# Handy_sense_v_1_0_2.net
KiCad netlist of a schematic drawn in EAGLE
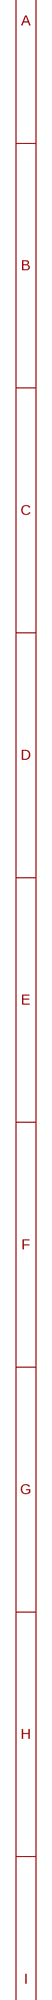
[diagram p0: schematic, sheet 1, part 1 of 2]
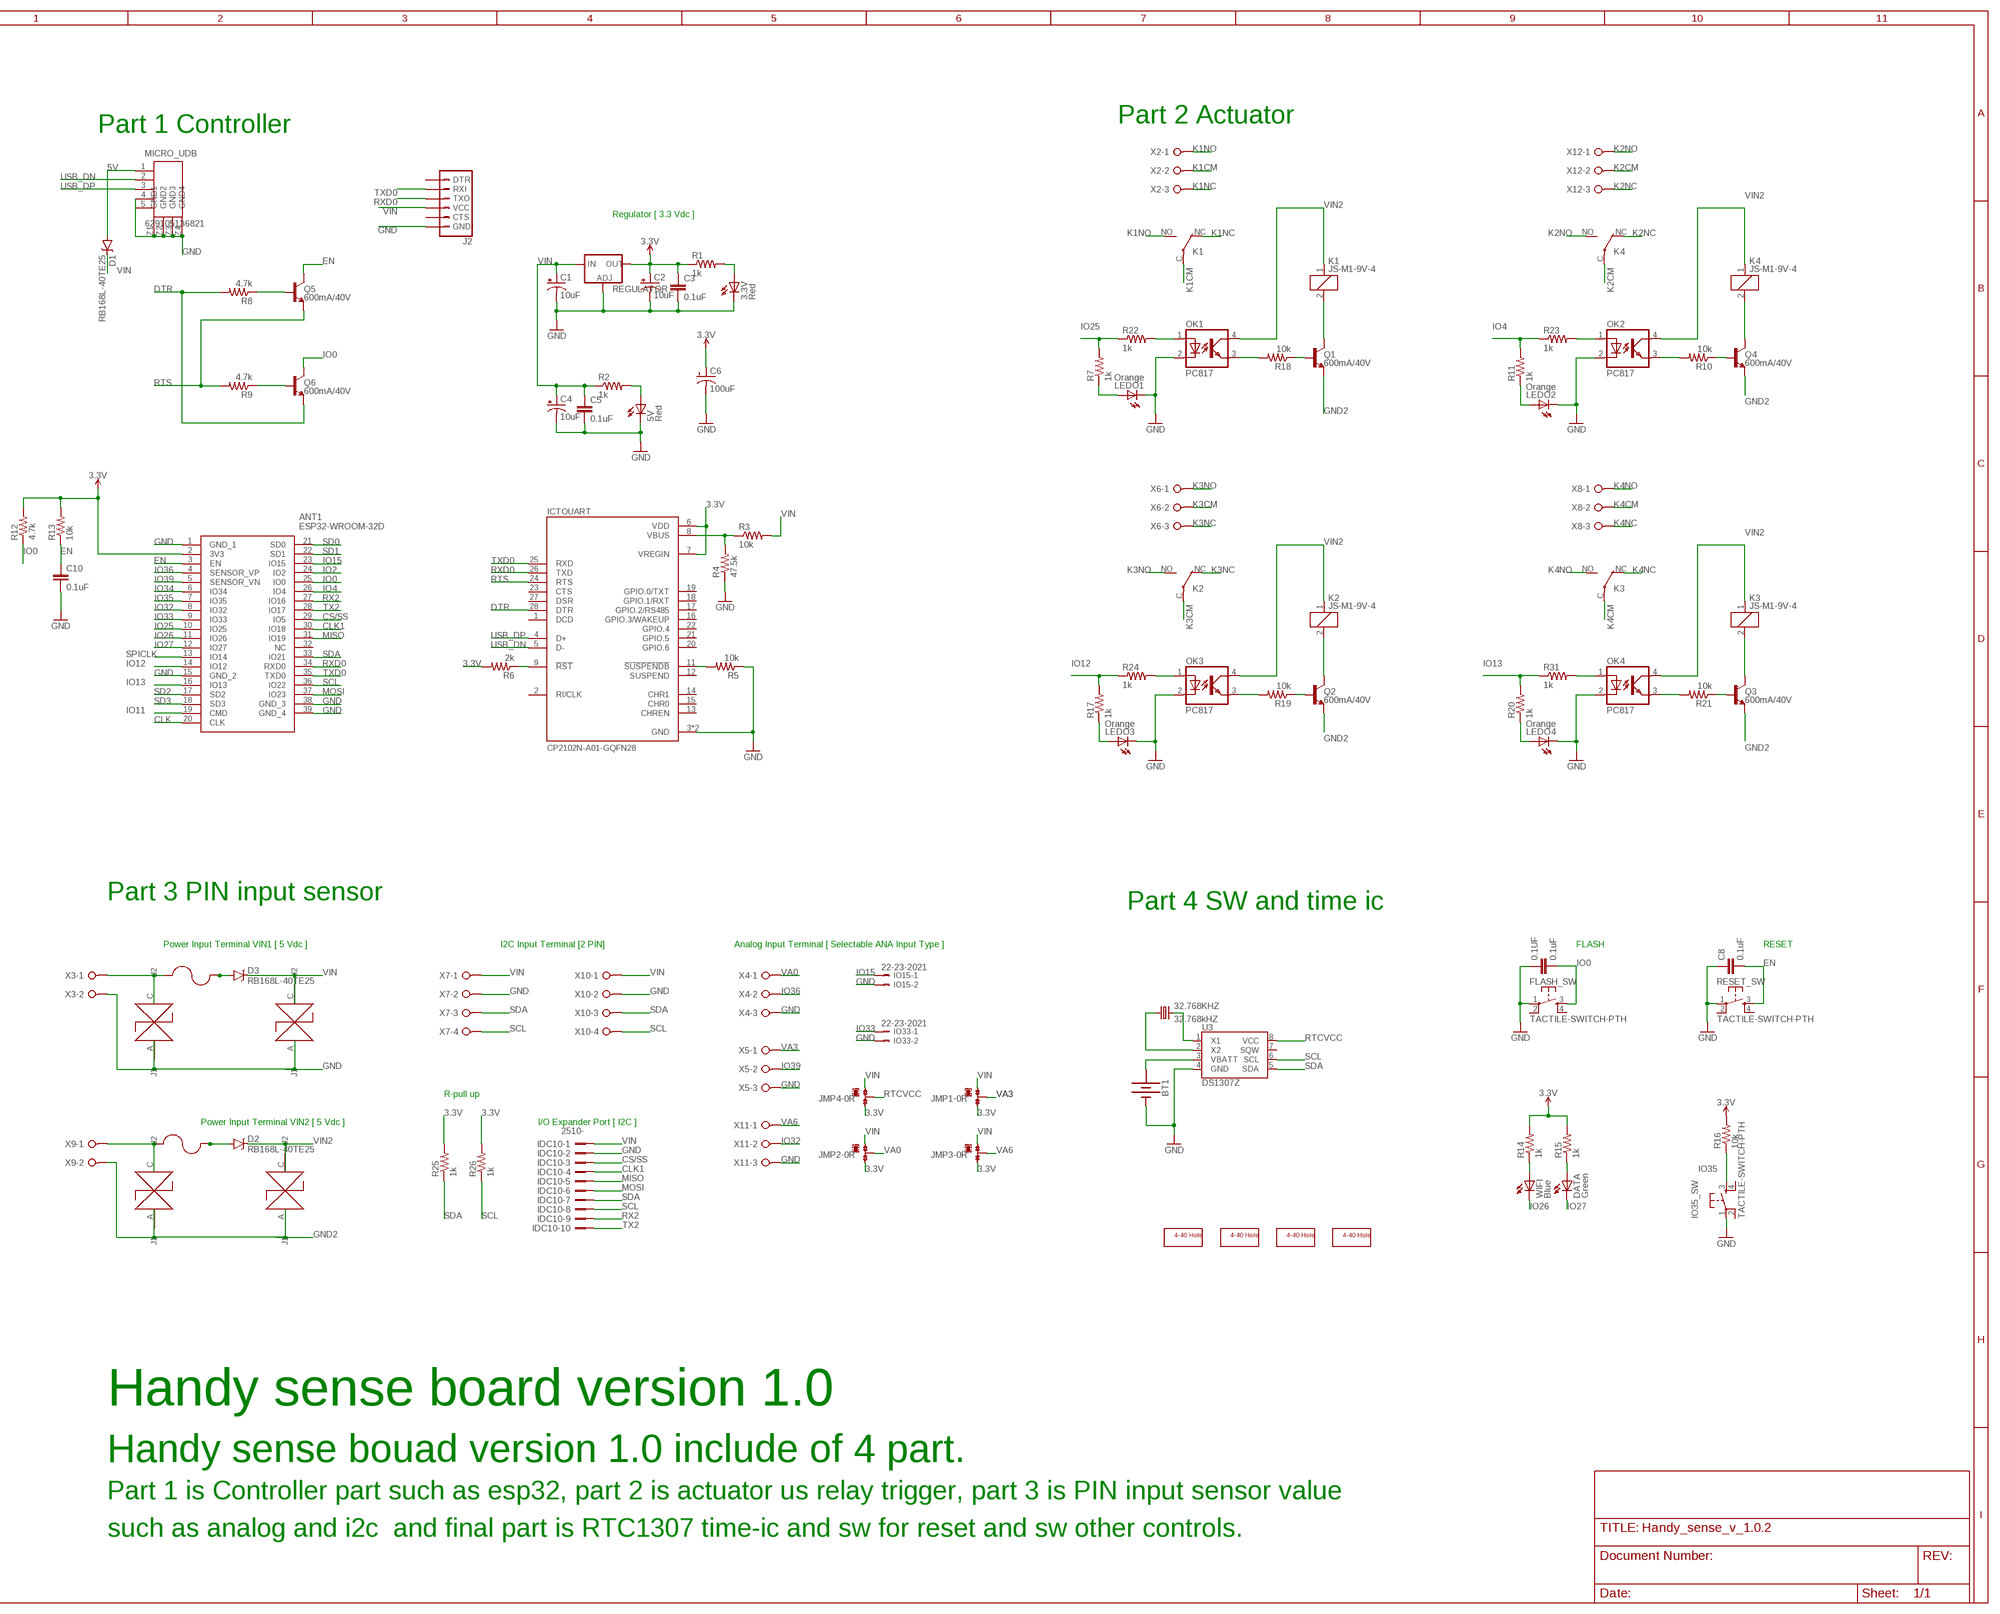
[diagram p1: schematic, sheet 1, part 2 of 2]

(export (version "E")
  (design (tool "Eeschema 10.0.6"))
  (components
    (comp (ref "0.1UF")
      (value "0.1uF")
      (footprint "eagle-import:0805")
      (libsource (lib "eagle-import") (part "CAP0805"))
    )
    (comp (ref "3.3V")
      (value "Red")
      (footprint "eagle-import:CHIPLED_0805")
      (libsource (lib "eagle-import") (part "LEDCHIPLED_0805"))
    )
    (comp (ref "5V")
      (value "Red")
      (footprint "eagle-import:CHIPLED_0805")
      (libsource (lib "eagle-import") (part "LEDCHIPLED_0805"))
    )
    (comp (ref "32.768KHZ")
      (value "32.768kHZ")
      (footprint "eagle-import:TC26H")
      (libsource (lib "eagle-import") (part "CRYSTALTC26H"))
    )
    (comp (ref "ANT1")
      (value "ESP32-WROOM-32D")
      (footprint "eagle-import:ESP32WROOM32D")
      (fields (field (name "MOUSER_PART_NUMBER") "356-ESP32WROOM-32D"))
      (libsource (lib "eagle-import") (part "ESP32-WROOM-32D"))
    )
    (comp (ref "BT1")
      (value "BATTERY-20MM_PTH_KIT")
      (footprint "eagle-import:BATTCOM_20MM_PTH_KIT")
      (libsource (lib "eagle-import") (part "BATTERY-20MM_PTH_KIT"))
    )
    (comp (ref "C1")
      (value "10uF")
      (footprint "eagle-import:EIA3216")
      (libsource (lib "eagle-import") (part "10UF-16V-10%(TANT)"))
    )
    (comp (ref "C2")
      (value "10uF")
      (footprint "eagle-import:EIA3216")
      (libsource (lib "eagle-import") (part "10UF-16V-10%(TANT)"))
    )
    (comp (ref "C3")
      (value "0.1uF")
      (footprint "eagle-import:0805")
      (libsource (lib "eagle-import") (part "CAP0805"))
    )
    (comp (ref "C4")
      (value "10uF")
      (footprint "eagle-import:EIA3216")
      (libsource (lib "eagle-import") (part "10UF-16V-10%(TANT)"))
    )
    (comp (ref "C5")
      (value "0.1uF")
      (footprint "eagle-import:0805")
      (libsource (lib "eagle-import") (part "CAP0805"))
    )
    (comp (ref "C6")
      (value "100uF")
      (footprint "eagle-import:EIA7343")
      (libsource (lib "eagle-import") (part "100UF-POLAR-EIA7343-16V-10%(TANT)"))
    )
    (comp (ref "C8")
      (value "0.1uF")
      (footprint "eagle-import:0805")
      (libsource (lib "eagle-import") (part "CAP0805"))
    )
    (comp (ref "C10")
      (value "0.1uF")
      (footprint "eagle-import:0805")
      (libsource (lib "eagle-import") (part "CAP0805"))
    )
    (comp (ref "D1")
      (value "RB168L-40TE25")
      (footprint "eagle-import:SMA-DIODE")
      (libsource (lib "eagle-import") (part "DIODE-SCHOTTKY-MBRA140"))
    )
    (comp (ref "D2")
      (value "RB168L-40TE25")
      (footprint "eagle-import:SMA-DIODE")
      (libsource (lib "eagle-import") (part "DIODE-SCHOTTKY-MBRA140"))
    )
    (comp (ref "D3")
      (value "RB168L-40TE25")
      (footprint "eagle-import:SMA-DIODE")
      (libsource (lib "eagle-import") (part "DIODE-SCHOTTKY-MBRA140"))
    )
    (comp (ref "DATA")
      (value "Green")
      (footprint "eagle-import:CHIPLED_0805")
      (libsource (lib "eagle-import") (part "LEDCHIPLED_0805"))
    )
    (comp (ref "FLASH_SW")
      (value "TACTILE-SWITCH-PTH")
      (footprint "eagle-import:TAC-SWITCH-PTH")
      (libsource (lib "eagle-import") (part "TACTILE-SWITCH-PTH"))
    )
    (comp (ref "HOLE0")
      (value "SCREW_HOLE_4-40")
      (footprint "eagle-import:SCREW_HOLE_4-40")
      (libsource (lib "eagle-import") (part "SCREW_HOLE_4-40"))
    )
    (comp (ref "HOLE1")
      (value "SCREW_HOLE_4-40")
      (footprint "eagle-import:SCREW_HOLE_4-40")
      (libsource (lib "eagle-import") (part "SCREW_HOLE_4-40"))
    )
    (comp (ref "HOLE2")
      (value "SCREW_HOLE_4-40")
      (footprint "eagle-import:SCREW_HOLE_4-40")
      (libsource (lib "eagle-import") (part "SCREW_HOLE_4-40"))
    )
    (comp (ref "HOLE3")
      (value "SCREW_HOLE_4-40")
      (footprint "eagle-import:SCREW_HOLE_4-40")
      (libsource (lib "eagle-import") (part "SCREW_HOLE_4-40"))
    )
    (comp (ref "ICTOUART")
      (value "CP2102N-A01-GQFN28")
      (footprint "eagle-import:QFN50P500X500X80-29N")
      (fields (field (name "MF") "Silicon Labs"))
      (libsource (lib "eagle-import") (part "CP2102N-A01-GQFN28"))
    )
    (comp (ref "IDC10")
      (value "2510-")
      (footprint "eagle-import:PAK100_2500-10")
      (fields (field (name "MF") "3M") (field (name "MPN") "2510-6002UB"))
      (libsource (lib "eagle-import") (part "2510-"))
    )
    (comp (ref "IO15")
      (value "22-23-2021")
      (footprint "eagle-import:22-23-2021")
      (fields (field (name "MF") "MOLEX"))
      (libsource (lib "eagle-import") (part "22-23-2021"))
    )
    (comp (ref "IO33")
      (value "22-23-2021")
      (footprint "eagle-import:22-23-2021")
      (fields (field (name "MF") "MOLEX"))
      (libsource (lib "eagle-import") (part "22-23-2021"))
    )
    (comp (ref "IO35_SW")
      (value "TACTILE-SWITCH-PTH")
      (footprint "eagle-import:TAC-SWITCH-PTH")
      (libsource (lib "eagle-import") (part "TACTILE-SWITCH-PTH"))
    )
    (comp (ref "J2")
      (value "6_PIN_SERIAL_TARGET_SILK")
      (footprint "eagle-import:1X06")
      (libsource (lib "eagle-import") (part "6_PIN_SERIAL_TARGET_SILK"))
    )
    (comp (ref "J28CA1")
      (value "SMBJ28CA")
      (footprint "eagle-import:DIOM505270X240")
      (libsource (lib "eagle-import") (part "SMBJ28CA"))
    )
    (comp (ref "J28CA3")
      (value "SMBJ28CA")
      (footprint "eagle-import:DIOM505270X240")
      (libsource (lib "eagle-import") (part "SMBJ28CA"))
    )
    (comp (ref "J28CA4")
      (value "SMBJ28CA")
      (footprint "eagle-import:DIOM505270X240")
      (libsource (lib "eagle-import") (part "SMBJ28CA"))
    )
    (comp (ref "J28CA6")
      (value "SMBJ28CA")
      (footprint "eagle-import:DIOM505270X240")
      (libsource (lib "eagle-import") (part "SMBJ28CA"))
    )
    (comp (ref "JMP1")
      (value "0R-JUMPB")
      (footprint "eagle-import:B0R-JMP")
      (libsource (lib "eagle-import") (part "0R-JUMPB"))
    )
    (comp (ref "JMP2")
      (value "0R-JUMPB")
      (footprint "eagle-import:B0R-JMP")
      (libsource (lib "eagle-import") (part "0R-JUMPB"))
    )
    (comp (ref "JMP3")
      (value "0R-JUMPB")
      (footprint "eagle-import:B0R-JMP")
      (libsource (lib "eagle-import") (part "0R-JUMPB"))
    )
    (comp (ref "JMP4")
      (value "0R-JUMPB")
      (footprint "eagle-import:B0R-JMP")
      (libsource (lib "eagle-import") (part "0R-JUMPB"))
    )
    (comp (ref "K1")
      (value "JS-M1-9V-4")
      (footprint "eagle-import:JS-M")
      (libsource (lib "eagle-import") (part "JS-M1-9V-4"))
    )
    (comp (ref "K2")
      (value "JS-M1-9V-4")
      (footprint "eagle-import:JS-M")
      (libsource (lib "eagle-import") (part "JS-M1-9V-4"))
    )
    (comp (ref "K3")
      (value "JS-M1-9V-4")
      (footprint "eagle-import:JS-M")
      (libsource (lib "eagle-import") (part "JS-M1-9V-4"))
    )
    (comp (ref "K4")
      (value "JS-M1-9V-4")
      (footprint "eagle-import:JS-M")
      (libsource (lib "eagle-import") (part "JS-M1-9V-4"))
    )
    (comp (ref "LEDO1")
      (value "Orange")
      (footprint "eagle-import:CHIPLED_0805")
      (libsource (lib "eagle-import") (part "LEDCHIPLED_0805"))
    )
    (comp (ref "LEDO2")
      (value "Orange")
      (footprint "eagle-import:CHIPLED_0805")
      (libsource (lib "eagle-import") (part "LEDCHIPLED_0805"))
    )
    (comp (ref "LEDO3")
      (value "Orange")
      (footprint "eagle-import:CHIPLED_0805")
      (libsource (lib "eagle-import") (part "LEDCHIPLED_0805"))
    )
    (comp (ref "LEDO4")
      (value "Orange")
      (footprint "eagle-import:CHIPLED_0805")
      (libsource (lib "eagle-import") (part "LEDCHIPLED_0805"))
    )
    (comp (ref "MICRO_UDB")
      (value "629105136821")
      (footprint "eagle-import:629105136821")
      (libsource (lib "eagle-import") (part "629105136821"))
    )
    (comp (ref "OK1")
      (value "PC817")
      (footprint "eagle-import:DIL04")
      (fields (field (name "MPN") "PC817X4J000F"))
      (libsource (lib "eagle-import") (part "PC817"))
    )
    (comp (ref "OK2")
      (value "PC817")
      (footprint "eagle-import:DIL04")
      (fields (field (name "MPN") "PC817X4J000F"))
      (libsource (lib "eagle-import") (part "PC817"))
    )
    (comp (ref "OK3")
      (value "PC817")
      (footprint "eagle-import:DIL04")
      (fields (field (name "MPN") "PC817X4J000F"))
      (libsource (lib "eagle-import") (part "PC817"))
    )
    (comp (ref "OK4")
      (value "PC817")
      (footprint "eagle-import:DIL04")
      (fields (field (name "MPN") "PC817X4J000F"))
      (libsource (lib "eagle-import") (part "PC817"))
    )
    (comp (ref "Q1")
      (value "600mA/40V")
      (footprint "eagle-import:SOT23-3")
      (libsource (lib "eagle-import") (part "TRANS_NPN-MMBT2222AL"))
    )
    (comp (ref "Q2")
      (value "600mA/40V")
      (footprint "eagle-import:SOT23-3")
      (libsource (lib "eagle-import") (part "TRANS_NPN-MMBT2222AL"))
    )
    (comp (ref "Q3")
      (value "600mA/40V")
      (footprint "eagle-import:SOT23-3")
      (libsource (lib "eagle-import") (part "TRANS_NPN-MMBT2222AL"))
    )
    (comp (ref "Q4")
      (value "600mA/40V")
      (footprint "eagle-import:SOT23-3")
      (libsource (lib "eagle-import") (part "TRANS_NPN-MMBT2222AL"))
    )
    (comp (ref "Q5")
      (value "600mA/40V")
      (footprint "eagle-import:SOT23-3")
      (libsource (lib "eagle-import") (part "TRANS_NPN-MMBT2222AL"))
    )
    (comp (ref "Q6")
      (value "600mA/40V")
      (footprint "eagle-import:SOT23-3")
      (libsource (lib "eagle-import") (part "TRANS_NPN-MMBT2222AL"))
    )
    (comp (ref "R1")
      (value "1k")
      (footprint "eagle-import:R0805")
      (libsource (lib "eagle-import") (part "R-US_R0805"))
    )
    (comp (ref "R2")
      (value "1k")
      (footprint "eagle-import:R0805")
      (libsource (lib "eagle-import") (part "R-US_R0805"))
    )
    (comp (ref "R3")
      (value "10k")
      (footprint "eagle-import:R0805")
      (libsource (lib "eagle-import") (part "R-US_R0805"))
    )
    (comp (ref "R4")
      (value "47.5k")
      (footprint "eagle-import:R0805")
      (libsource (lib "eagle-import") (part "R-US_R0805"))
    )
    (comp (ref "R5")
      (value "10k")
      (footprint "eagle-import:R0805")
      (libsource (lib "eagle-import") (part "R-US_R0805"))
    )
    (comp (ref "R6")
      (value "2k")
      (footprint "eagle-import:R0805")
      (libsource (lib "eagle-import") (part "R-US_R0805"))
    )
    (comp (ref "R7")
      (value "1k")
      (footprint "eagle-import:R0805")
      (libsource (lib "eagle-import") (part "R-US_R0805"))
    )
    (comp (ref "R8")
      (value "4.7k")
      (footprint "eagle-import:R0805")
      (libsource (lib "eagle-import") (part "R-US_R0805"))
    )
    (comp (ref "R9")
      (value "4.7k")
      (footprint "eagle-import:R0805")
      (libsource (lib "eagle-import") (part "R-US_R0805"))
    )
    (comp (ref "R10")
      (value "10k")
      (footprint "eagle-import:R0805")
      (libsource (lib "eagle-import") (part "R-US_R0805"))
    )
    (comp (ref "R11")
      (value "1k")
      (footprint "eagle-import:R0805")
      (libsource (lib "eagle-import") (part "R-US_R0805"))
    )
    (comp (ref "R12")
      (value "4.7k")
      (footprint "eagle-import:R0805")
      (libsource (lib "eagle-import") (part "R-US_R0805"))
    )
    (comp (ref "R13")
      (value "10k")
      (footprint "eagle-import:R0805")
      (libsource (lib "eagle-import") (part "R-US_R0805"))
    )
    (comp (ref "R14")
      (value "1k")
      (footprint "eagle-import:R0805")
      (libsource (lib "eagle-import") (part "R-US_R0805"))
    )
    (comp (ref "R15")
      (value "1k")
      (footprint "eagle-import:R0805")
      (libsource (lib "eagle-import") (part "R-US_R0805"))
    )
    (comp (ref "R16")
      (value "10k")
      (footprint "eagle-import:R0805")
      (libsource (lib "eagle-import") (part "R-US_R0805"))
    )
    (comp (ref "R17")
      (value "1k")
      (footprint "eagle-import:R0805")
      (libsource (lib "eagle-import") (part "R-US_R0805"))
    )
    (comp (ref "R18")
      (value "10k")
      (footprint "eagle-import:R0805")
      (libsource (lib "eagle-import") (part "R-US_R0805"))
    )
    (comp (ref "R19")
      (value "10k")
      (footprint "eagle-import:R0805")
      (libsource (lib "eagle-import") (part "R-US_R0805"))
    )
    (comp (ref "R20")
      (value "1k")
      (footprint "eagle-import:R0805")
      (libsource (lib "eagle-import") (part "R-US_R0805"))
    )
    (comp (ref "R21")
      (value "10k")
      (footprint "eagle-import:R0805")
      (libsource (lib "eagle-import") (part "R-US_R0805"))
    )
    (comp (ref "R22")
      (value "1k")
      (footprint "eagle-import:R0805")
      (libsource (lib "eagle-import") (part "R-US_R0805"))
    )
    (comp (ref "R23")
      (value "1k")
      (footprint "eagle-import:R0805")
      (libsource (lib "eagle-import") (part "R-US_R0805"))
    )
    (comp (ref "R24")
      (value "1k")
      (footprint "eagle-import:R0805")
      (libsource (lib "eagle-import") (part "R-US_R0805"))
    )
    (comp (ref "R25")
      (value "1k")
      (footprint "eagle-import:R0805")
      (libsource (lib "eagle-import") (part "R-US_R0805"))
    )
    (comp (ref "R26")
      (value "1k")
      (footprint "eagle-import:R0805")
      (libsource (lib "eagle-import") (part "R-US_R0805"))
    )
    (comp (ref "R31")
      (value "1k")
      (footprint "eagle-import:R0805")
      (libsource (lib "eagle-import") (part "R-US_R0805"))
    )
    (comp (ref "REGULATOR")
      (value "V_REG_LM1117SOT223")
      (footprint "eagle-import:SOT223")
      (libsource (lib "eagle-import") (part "V_REG_LM1117SOT223"))
    )
    (comp (ref "RESET_SW")
      (value "TACTILE-SWITCH-PTH")
      (footprint "eagle-import:TAC-SWITCH-PTH")
      (libsource (lib "eagle-import") (part "TACTILE-SWITCH-PTH"))
    )
    (comp (ref "U$1")
      (value "MSMFF2602")
      (footprint "eagle-import:FUSE_MF-MSMF260-2")
      (libsource (lib "eagle-import") (part "MSMFF2602"))
    )
    (comp (ref "U$2")
      (value "MSMFF2602")
      (footprint "eagle-import:FUSE_MF-MSMF260-2")
      (libsource (lib "eagle-import") (part "MSMFF2602"))
    )
    (comp (ref "U3")
      (value "DS1307Z")
      (footprint "eagle-import:SO08-0.15")
      (libsource (lib "eagle-import") (part "DS1307Z"))
    )
    (comp (ref "WIFI")
      (value "Blue")
      (footprint "eagle-import:CHIPLED_0805")
      (libsource (lib "eagle-import") (part "LEDCHIPLED_0805"))
    )
    (comp (ref "X2")
      (value "W237-03P")
      (footprint "eagle-import:W237-133")
      (libsource (lib "eagle-import") (part "W237-03P"))
    )
    (comp (ref "X3")
      (value "W237-02P")
      (footprint "eagle-import:W237-132")
      (libsource (lib "eagle-import") (part "W237-02P"))
    )
    (comp (ref "X4")
      (value "W237-03P")
      (footprint "eagle-import:W237-133")
      (libsource (lib "eagle-import") (part "W237-03P"))
    )
    (comp (ref "X5")
      (value "W237-03P")
      (footprint "eagle-import:W237-133")
      (libsource (lib "eagle-import") (part "W237-03P"))
    )
    (comp (ref "X6")
      (value "W237-03P")
      (footprint "eagle-import:W237-133")
      (libsource (lib "eagle-import") (part "W237-03P"))
    )
    (comp (ref "X7")
      (value "W237-04P")
      (footprint "eagle-import:W237-4P")
      (libsource (lib "eagle-import") (part "W237-04P"))
    )
    (comp (ref "X8")
      (value "W237-03P")
      (footprint "eagle-import:W237-133")
      (libsource (lib "eagle-import") (part "W237-03P"))
    )
    (comp (ref "X9")
      (value "W237-02P")
      (footprint "eagle-import:W237-132")
      (libsource (lib "eagle-import") (part "W237-02P"))
    )
    (comp (ref "X10")
      (value "W237-04P")
      (footprint "eagle-import:W237-4P")
      (libsource (lib "eagle-import") (part "W237-04P"))
    )
    (comp (ref "X11")
      (value "W237-03P")
      (footprint "eagle-import:W237-133")
      (libsource (lib "eagle-import") (part "W237-03P"))
    )
    (comp (ref "X12")
      (value "W237-03P")
      (footprint "eagle-import:W237-133")
      (libsource (lib "eagle-import") (part "W237-03P"))
    )
  )
  (nets
    (net (code "1") (name "/5V") (class "Default")
      (node (ref "D1") (pin "A") (pinfunction "A_A") (pintype "passive"))
      (node (ref "MICRO_UDB") (pin "1") (pinfunction "+5V_1") (pintype "passive"))
    )
    (net (code "2") (name "/CLK") (class "Default")
      (node (ref "ANT1") (pin "20") (pinfunction "CLK_20") (pintype "bidirectional"))
    )
    (net (code "3") (name "/CLK1") (class "Default")
      (node (ref "ANT1") (pin "30") (pinfunction "IO18_30") (pintype "bidirectional"))
      (node (ref "IDC10") (pin "4") (pinfunction "KL_4") (pintype "passive"))
    )
    (net (code "4") (name "/CS{slash}SS") (class "Default")
      (node (ref "ANT1") (pin "29") (pinfunction "IO5_29") (pintype "bidirectional"))
      (node (ref "IDC10") (pin "3") (pinfunction "KL_3") (pintype "passive"))
    )
    (net (code "5") (name "/DTR") (class "Default")
      (node (ref "ICTOUART") (pin "28") (pinfunction "DTR_28") (pintype "output"))
      (node (ref "Q6") (pin "2") (pinfunction "E_2") (pintype "passive"))
      (node (ref "R8") (pin "2") (pinfunction "2_2") (pintype "passive"))
    )
    (net (code "6") (name "/EN") (class "Default")
      (node (ref "ANT1") (pin "3") (pinfunction "EN_3") (pintype "bidirectional"))
      (node (ref "C10") (pin "1") (pinfunction "1_1") (pintype "passive"))
      (node (ref "C8") (pin "2") (pinfunction "2_2") (pintype "passive"))
      (node (ref "Q5") (pin "3") (pinfunction "C_3") (pintype "passive"))
      (node (ref "R13") (pin "1") (pinfunction "1_1") (pintype "passive"))
      (node (ref "RESET_SW") (pin "3") (pinfunction "3_3") (pintype "passive"))
    )
    (net (code "7") (name "/GND2") (class "Default")
      (node (ref "J28CA4") (pin "A") (pinfunction "J1_A") (pintype "bidirectional"))
      (node (ref "J28CA6") (pin "A") (pinfunction "J1_A") (pintype "bidirectional"))
      (node (ref "Q1") (pin "2") (pinfunction "E_2") (pintype "passive"))
      (node (ref "Q2") (pin "2") (pinfunction "E_2") (pintype "passive"))
      (node (ref "Q3") (pin "2") (pinfunction "E_2") (pintype "passive"))
      (node (ref "Q4") (pin "2") (pinfunction "E_2") (pintype "passive"))
      (node (ref "X9") (pin "2") (pinfunction "KL_2") (pintype "passive"))
    )
    (net (code "8") (name "/IO0") (class "Default")
      (node (ref "0.1UF") (pin "2") (pinfunction "2_2") (pintype "passive"))
      (node (ref "ANT1") (pin "25") (pinfunction "IO0_25") (pintype "bidirectional"))
      (node (ref "FLASH_SW") (pin "3") (pinfunction "3_3") (pintype "passive"))
      (node (ref "Q6") (pin "3") (pinfunction "C_3") (pintype "passive"))
      (node (ref "R12") (pin "1") (pinfunction "1_1") (pintype "passive"))
    )
    (net (code "9") (name "/IO2") (class "Default")
      (node (ref "ANT1") (pin "24") (pinfunction "IO2_24") (pintype "bidirectional"))
    )
    (net (code "10") (name "/IO4") (class "Default")
      (node (ref "ANT1") (pin "26") (pinfunction "IO4_26") (pintype "bidirectional"))
      (node (ref "R11") (pin "2") (pinfunction "2_2") (pintype "passive"))
      (node (ref "R23") (pin "1") (pinfunction "1_1") (pintype "passive"))
    )
    (net (code "11") (name "/IO11") (class "Default")
      (node (ref "ANT1") (pin "19") (pinfunction "CMD_19") (pintype "bidirectional"))
    )
    (net (code "12") (name "/IO12") (class "Default")
      (node (ref "ANT1") (pin "14") (pinfunction "IO12_14") (pintype "bidirectional"))
      (node (ref "R17") (pin "2") (pinfunction "2_2") (pintype "passive"))
      (node (ref "R24") (pin "1") (pinfunction "1_1") (pintype "passive"))
    )
    (net (code "13") (name "/IO13") (class "Default")
      (node (ref "ANT1") (pin "16") (pinfunction "IO13_16") (pintype "bidirectional"))
      (node (ref "R20") (pin "2") (pinfunction "2_2") (pintype "passive"))
      (node (ref "R31") (pin "1") (pinfunction "1_1") (pintype "passive"))
    )
    (net (code "14") (name "/IO15") (class "Default")
      (node (ref "ANT1") (pin "23") (pinfunction "IO15_23") (pintype "bidirectional"))
      (node (ref "IO15") (pin "1") (pinfunction "S_1") (pintype "passive"))
    )
    (net (code "15") (name "/IO25") (class "Default")
      (node (ref "ANT1") (pin "10") (pinfunction "IO25_10") (pintype "bidirectional"))
      (node (ref "R22") (pin "1") (pinfunction "1_1") (pintype "passive"))
      (node (ref "R7") (pin "2") (pinfunction "2_2") (pintype "passive"))
    )
    (net (code "16") (name "/IO26") (class "Default")
      (node (ref "ANT1") (pin "11") (pinfunction "IO26_11") (pintype "bidirectional"))
      (node (ref "WIFI") (pin "C") (pinfunction "C_C") (pintype "passive"))
    )
    (net (code "17") (name "/IO27") (class "Default")
      (node (ref "ANT1") (pin "12") (pinfunction "IO27_12") (pintype "bidirectional"))
      (node (ref "DATA") (pin "C") (pinfunction "C_C") (pintype "passive"))
    )
    (net (code "18") (name "/IO32") (class "Default")
      (node (ref "ANT1") (pin "8") (pinfunction "IO32_8") (pintype "bidirectional"))
      (node (ref "X11") (pin "2") (pinfunction "KL_2") (pintype "passive"))
    )
    (net (code "19") (name "/IO33") (class "Default")
      (node (ref "ANT1") (pin "9") (pinfunction "IO33_9") (pintype "bidirectional"))
      (node (ref "IO33") (pin "1") (pinfunction "S_1") (pintype "passive"))
    )
    (net (code "20") (name "/IO34") (class "Default")
      (node (ref "ANT1") (pin "6") (pinfunction "IO34_6") (pintype "bidirectional"))
    )
    (net (code "21") (name "/IO35") (class "Default")
      (node (ref "ANT1") (pin "7") (pinfunction "IO35_7") (pintype "bidirectional"))
      (node (ref "IO35_SW") (pin "3") (pinfunction "3_3") (pintype "passive"))
      (node (ref "R16") (pin "1") (pinfunction "1_1") (pintype "passive"))
    )
    (net (code "22") (name "/IO36") (class "Default")
      (node (ref "ANT1") (pin "4") (pinfunction "SENSOR_VP_4") (pintype "bidirectional"))
      (node (ref "X4") (pin "2") (pinfunction "KL_2") (pintype "passive"))
    )
    (net (code "23") (name "/IO39") (class "Default")
      (node (ref "ANT1") (pin "5") (pinfunction "SENSOR_VN_5") (pintype "bidirectional"))
      (node (ref "X5") (pin "2") (pinfunction "KL_2") (pintype "passive"))
    )
    (net (code "24") (name "/K1CM") (class "Default")
      (node (ref "K1") (pin "C") (pinfunction "P_C") (pintype "passive"))
      (node (ref "X2") (pin "2") (pinfunction "KL_2") (pintype "passive"))
    )
    (net (code "25") (name "/K1NC") (class "Default")
      (node (ref "K1") (pin "NC") (pinfunction "O_NC") (pintype "passive"))
      (node (ref "X2") (pin "3") (pinfunction "KL_3") (pintype "passive"))
    )
    (net (code "26") (name "/K1NO") (class "Default")
      (node (ref "K1") (pin "NO") (pinfunction "S_NO") (pintype "passive"))
      (node (ref "X2") (pin "1") (pinfunction "KL_1") (pintype "passive"))
    )
    (net (code "27") (name "/K2CM") (class "Default")
      (node (ref "K4") (pin "C") (pinfunction "P_C") (pintype "passive"))
      (node (ref "X12") (pin "2") (pinfunction "KL_2") (pintype "passive"))
    )
    (net (code "28") (name "/K2NC") (class "Default")
      (node (ref "K4") (pin "NC") (pinfunction "O_NC") (pintype "passive"))
      (node (ref "X12") (pin "3") (pinfunction "KL_3") (pintype "passive"))
    )
    (net (code "29") (name "/K2NO") (class "Default")
      (node (ref "K4") (pin "NO") (pinfunction "S_NO") (pintype "passive"))
      (node (ref "X12") (pin "1") (pinfunction "KL_1") (pintype "passive"))
    )
    (net (code "30") (name "/K3CM") (class "Default")
      (node (ref "K2") (pin "C") (pinfunction "P_C") (pintype "passive"))
      (node (ref "X6") (pin "2") (pinfunction "KL_2") (pintype "passive"))
    )
    (net (code "31") (name "/K3NC") (class "Default")
      (node (ref "K2") (pin "NC") (pinfunction "O_NC") (pintype "passive"))
      (node (ref "X6") (pin "3") (pinfunction "KL_3") (pintype "passive"))
    )
    (net (code "32") (name "/K3NO") (class "Default")
      (node (ref "K2") (pin "NO") (pinfunction "S_NO") (pintype "passive"))
      (node (ref "X6") (pin "1") (pinfunction "KL_1") (pintype "passive"))
    )
    (net (code "33") (name "/K4CM") (class "Default")
      (node (ref "K3") (pin "C") (pinfunction "P_C") (pintype "passive"))
      (node (ref "X8") (pin "2") (pinfunction "KL_2") (pintype "passive"))
    )
    (net (code "34") (name "/K4NC") (class "Default")
      (node (ref "K3") (pin "NC") (pinfunction "O_NC") (pintype "passive"))
      (node (ref "X8") (pin "3") (pinfunction "KL_3") (pintype "passive"))
    )
    (net (code "35") (name "/K4NO") (class "Default")
      (node (ref "K3") (pin "NO") (pinfunction "S_NO") (pintype "passive"))
      (node (ref "X8") (pin "1") (pinfunction "KL_1") (pintype "passive"))
    )
    (net (code "36") (name "/MISO") (class "Default")
      (node (ref "ANT1") (pin "31") (pinfunction "IO19_31") (pintype "bidirectional"))
      (node (ref "IDC10") (pin "5") (pinfunction "KL_5") (pintype "passive"))
    )
    (net (code "37") (name "/MOSI") (class "Default")
      (node (ref "ANT1") (pin "37") (pinfunction "IO23_37") (pintype "bidirectional"))
      (node (ref "IDC10") (pin "6") (pinfunction "KL_6") (pintype "passive"))
    )
    (net (code "38") (name "/RTCVCC") (class "Default")
      (node (ref "JMP4") (pin "2") (pinfunction "2_2") (pintype "passive"))
      (node (ref "U3") (pin "8") (pinfunction "VCC_8") (pintype "bidirectional"))
    )
    (net (code "39") (name "/RTS") (class "Default")
      (node (ref "ICTOUART") (pin "24") (pinfunction "RTS_24") (pintype "output"))
      (node (ref "Q5") (pin "2") (pinfunction "E_2") (pintype "passive"))
      (node (ref "R9") (pin "2") (pinfunction "2_2") (pintype "passive"))
    )
    (net (code "40") (name "/RX2") (class "Default")
      (node (ref "ANT1") (pin "27") (pinfunction "IO16_27") (pintype "bidirectional"))
      (node (ref "IDC10") (pin "9") (pinfunction "KL_9") (pintype "passive"))
    )
    (net (code "41") (name "/RXD0") (class "Default")
      (node (ref "ANT1") (pin "34") (pinfunction "RXD0_34") (pintype "bidirectional"))
      (node (ref "ICTOUART") (pin "26") (pinfunction "TXD_26") (pintype "output"))
      (node (ref "J2") (pin "3") (pinfunction "TXO_3") (pintype "passive"))
    )
    (net (code "42") (name "/SCL") (class "Default")
      (node (ref "ANT1") (pin "36") (pinfunction "IO22_36") (pintype "bidirectional"))
      (node (ref "IDC10") (pin "8") (pinfunction "KL_8") (pintype "passive"))
      (node (ref "R26") (pin "1") (pinfunction "1_1") (pintype "passive"))
      (node (ref "U3") (pin "6") (pinfunction "SCL_6") (pintype "bidirectional"))
      (node (ref "X10") (pin "4") (pinfunction "KL_4") (pintype "passive"))
      (node (ref "X7") (pin "4") (pinfunction "KL_4") (pintype "passive"))
    )
    (net (code "43") (name "/SD0") (class "Default")
      (node (ref "ANT1") (pin "21") (pinfunction "SD0_21") (pintype "bidirectional"))
    )
    (net (code "44") (name "/SD1") (class "Default")
      (node (ref "ANT1") (pin "22") (pinfunction "SD1_22") (pintype "bidirectional"))
    )
    (net (code "45") (name "/SD2") (class "Default")
      (node (ref "ANT1") (pin "17") (pinfunction "SD2_17") (pintype "bidirectional"))
    )
    (net (code "46") (name "/SD3") (class "Default")
      (node (ref "ANT1") (pin "18") (pinfunction "SD3_18") (pintype "bidirectional"))
    )
    (net (code "47") (name "/SDA") (class "Default")
      (node (ref "ANT1") (pin "33") (pinfunction "IO21_33") (pintype "bidirectional"))
      (node (ref "IDC10") (pin "7") (pinfunction "KL_7") (pintype "passive"))
      (node (ref "R25") (pin "1") (pinfunction "1_1") (pintype "passive"))
      (node (ref "U3") (pin "5") (pinfunction "SDA_5") (pintype "bidirectional"))
      (node (ref "X10") (pin "3") (pinfunction "KL_3") (pintype "passive"))
      (node (ref "X7") (pin "3") (pinfunction "KL_3") (pintype "passive"))
    )
    (net (code "48") (name "/SPICLK") (class "Default")
      (node (ref "ANT1") (pin "13") (pinfunction "IO14_13") (pintype "bidirectional"))
    )
    (net (code "49") (name "/TX2") (class "Default")
      (node (ref "ANT1") (pin "28") (pinfunction "IO17_28") (pintype "bidirectional"))
      (node (ref "IDC10") (pin "10") (pinfunction "KL_10") (pintype "passive"))
    )
    (net (code "50") (name "/TXD0") (class "Default")
      (node (ref "ANT1") (pin "35") (pinfunction "TXD0_35") (pintype "bidirectional"))
      (node (ref "ICTOUART") (pin "25") (pinfunction "RXD_25") (pintype "input"))
      (node (ref "J2") (pin "2") (pinfunction "RXI_2") (pintype "passive"))
    )
    (net (code "51") (name "/USB_DN") (class "Default")
      (node (ref "ICTOUART") (pin "5") (pinfunction "D-_5") (pintype "bidirectional"))
      (node (ref "MICRO_UDB") (pin "2") (pinfunction "D-_2") (pintype "passive"))
    )
    (net (code "52") (name "/USB_DP") (class "Default")
      (node (ref "ICTOUART") (pin "4") (pinfunction "D+_4") (pintype "bidirectional"))
      (node (ref "MICRO_UDB") (pin "3") (pinfunction "D+_3") (pintype "passive"))
    )
    (net (code "53") (name "/VA0") (class "Default")
      (node (ref "JMP2") (pin "2") (pinfunction "2_2") (pintype "passive"))
      (node (ref "X4") (pin "1") (pinfunction "KL_1") (pintype "passive"))
    )
    (net (code "54") (name "/VA3") (class "Default")
      (node (ref "JMP1") (pin "2") (pinfunction "2_2") (pintype "passive"))
      (node (ref "X5") (pin "1") (pinfunction "KL_1") (pintype "passive"))
    )
    (net (code "55") (name "/VA6") (class "Default")
      (node (ref "JMP3") (pin "2") (pinfunction "2_2") (pintype "passive"))
      (node (ref "X11") (pin "1") (pinfunction "KL_1") (pintype "passive"))
    )
    (net (code "56") (name "/VIN") (class "Default")
      (node (ref "C1") (pin "A") (pinfunction "+_A") (pintype "passive"))
      (node (ref "C4") (pin "A") (pinfunction "+_A") (pintype "passive"))
      (node (ref "C5") (pin "1") (pinfunction "1_1") (pintype "passive"))
      (node (ref "D1") (pin "C") (pinfunction "C_C") (pintype "passive"))
      (node (ref "D3") (pin "C") (pinfunction "C_C") (pintype "passive"))
      (node (ref "IDC10") (pin "1") (pinfunction "KL_1") (pintype "passive"))
      (node (ref "J2") (pin "4") (pinfunction "VCC_4") (pintype "passive"))
      (node (ref "J28CA3") (pin "C") (pinfunction "J2_C") (pintype "bidirectional"))
      (node (ref "JMP1") (pin "1") (pinfunction "1_1") (pintype "passive"))
      (node (ref "JMP2") (pin "1") (pinfunction "1_1") (pintype "passive"))
      (node (ref "JMP3") (pin "1") (pinfunction "1_1") (pintype "passive"))
      (node (ref "JMP4") (pin "1") (pinfunction "1_1") (pintype "passive"))
      (node (ref "R2") (pin "1") (pinfunction "1_1") (pintype "passive"))
      (node (ref "R3") (pin "2") (pinfunction "2_2") (pintype "passive"))
      (node (ref "REGULATOR") (pin "3") (pinfunction "IN_3") (pintype "input"))
      (node (ref "X10") (pin "1") (pinfunction "KL_1") (pintype "passive"))
      (node (ref "X7") (pin "1") (pinfunction "KL_1") (pintype "passive"))
    )
    (net (code "57") (name "/VIN2") (class "Default")
      (node (ref "D2") (pin "C") (pinfunction "C_C") (pintype "passive"))
      (node (ref "J28CA6") (pin "C") (pinfunction "J2_C") (pintype "bidirectional"))
      (node (ref "K1") (pin "1") (pinfunction "1_1") (pintype "passive"))
      (node (ref "K2") (pin "1") (pinfunction "1_1") (pintype "passive"))
      (node (ref "K3") (pin "1") (pinfunction "1_1") (pintype "passive"))
      (node (ref "K4") (pin "1") (pinfunction "1_1") (pintype "passive"))
      (node (ref "OK1") (pin "4") (pinfunction "COL_4") (pintype "passive"))
      (node (ref "OK2") (pin "4") (pinfunction "COL_4") (pintype "passive"))
      (node (ref "OK3") (pin "4") (pinfunction "COL_4") (pintype "passive"))
      (node (ref "OK4") (pin "4") (pinfunction "COL_4") (pintype "passive"))
    )
    (net (code "58") (name "3.3V") (class "Default")
      (node (ref "ANT1") (pin "2") (pinfunction "3V3_2") (pintype "bidirectional"))
      (node (ref "C2") (pin "A") (pinfunction "+_A") (pintype "passive"))
      (node (ref "C3") (pin "1") (pinfunction "1_1") (pintype "passive"))
      (node (ref "C6") (pin "A") (pinfunction "+_A") (pintype "passive"))
      (node (ref "ICTOUART") (pin "6") (pinfunction "VDD_6") (pintype "power_in"))
      (node (ref "ICTOUART") (pin "7") (pinfunction "VREGIN_7") (pintype "power_in"))
      (node (ref "JMP1") (pin "3") (pinfunction "3_3") (pintype "passive"))
      (node (ref "JMP2") (pin "3") (pinfunction "3_3") (pintype "passive"))
      (node (ref "JMP3") (pin "3") (pinfunction "3_3") (pintype "passive"))
      (node (ref "JMP4") (pin "3") (pinfunction "3_3") (pintype "passive"))
      (node (ref "R1") (pin "1") (pinfunction "1_1") (pintype "passive"))
      (node (ref "R12") (pin "2") (pinfunction "2_2") (pintype "passive"))
      (node (ref "R13") (pin "2") (pinfunction "2_2") (pintype "passive"))
      (node (ref "R14") (pin "2") (pinfunction "2_2") (pintype "passive"))
      (node (ref "R15") (pin "2") (pinfunction "2_2") (pintype "passive"))
      (node (ref "R16") (pin "2") (pinfunction "2_2") (pintype "passive"))
      (node (ref "R25") (pin "2") (pinfunction "2_2") (pintype "passive"))
      (node (ref "R26") (pin "2") (pinfunction "2_2") (pintype "passive"))
      (node (ref "R6") (pin "2") (pinfunction "2_2") (pintype "passive"))
      (node (ref "REGULATOR") (pin "2") (pinfunction "OUT_2") (pintype "output"))
      (node (ref "REGULATOR") (pin "4") (pinfunction "OUT_4") (pintype "output"))
    )
    (net (code "59") (name "GND") (class "Default")
      (node (ref "0.1UF") (pin "1") (pinfunction "1_1") (pintype "passive"))
      (node (ref "3.3V") (pin "C") (pinfunction "C_C") (pintype "passive"))
      (node (ref "5V") (pin "C") (pinfunction "C_C") (pintype "passive"))
      (node (ref "ANT1") (pin "1") (pinfunction "GND_1_1") (pintype "bidirectional"))
      (node (ref "ANT1") (pin "15") (pinfunction "GND_2_15") (pintype "bidirectional"))
      (node (ref "ANT1") (pin "38") (pinfunction "GND_3_38") (pintype "bidirectional"))
      (node (ref "ANT1") (pin "39") (pinfunction "GND_4_39") (pintype "bidirectional"))
      (node (ref "BT1") (pin "2") (pinfunction "-_2") (pintype "power_in"))
      (node (ref "C1") (pin "C") (pinfunction "-_C") (pintype "passive"))
      (node (ref "C10") (pin "2") (pinfunction "2_2") (pintype "passive"))
      (node (ref "C2") (pin "C") (pinfunction "-_C") (pintype "passive"))
      (node (ref "C3") (pin "2") (pinfunction "2_2") (pintype "passive"))
      (node (ref "C4") (pin "C") (pinfunction "-_C") (pintype "passive"))
      (node (ref "C5") (pin "2") (pinfunction "2_2") (pintype "passive"))
      (node (ref "C6") (pin "C") (pinfunction "-_C") (pintype "passive"))
      (node (ref "C8") (pin "1") (pinfunction "1_1") (pintype "passive"))
      (node (ref "FLASH_SW") (pin "1") (pinfunction "1_1") (pintype "passive"))
      (node (ref "ICTOUART") (pin "29") (pinfunction "GND_29") (pintype "power_in"))
      (node (ref "ICTOUART") (pin "3") (pinfunction "GND_3") (pintype "power_in"))
      (node (ref "IDC10") (pin "2") (pinfunction "KL_2") (pintype "passive"))
      (node (ref "IO15") (pin "2") (pinfunction "S_2") (pintype "passive"))
      (node (ref "IO33") (pin "2") (pinfunction "S_2") (pintype "passive"))
      (node (ref "IO35_SW") (pin "1") (pinfunction "1_1") (pintype "passive"))
      (node (ref "J2") (pin "6") (pinfunction "GND_6") (pintype "passive"))
      (node (ref "J28CA1") (pin "A") (pinfunction "J1_A") (pintype "bidirectional"))
      (node (ref "J28CA3") (pin "A") (pinfunction "J1_A") (pintype "bidirectional"))
      (node (ref "LEDO1") (pin "C") (pinfunction "C_C") (pintype "passive"))
      (node (ref "LEDO2") (pin "C") (pinfunction "C_C") (pintype "passive"))
      (node (ref "LEDO3") (pin "C") (pinfunction "C_C") (pintype "passive"))
      (node (ref "LEDO4") (pin "C") (pinfunction "C_C") (pintype "passive"))
      (node (ref "MICRO_UDB") (pin "4") (pinfunction "ID_4") (pintype "passive"))
      (node (ref "MICRO_UDB") (pin "5") (pinfunction "GND_5") (pintype "passive"))
      (node (ref "MICRO_UDB") (pin "Z1") (pinfunction "GND1_Z1") (pintype "bidirectional"))
      (node (ref "MICRO_UDB") (pin "Z2") (pinfunction "GND2_Z2") (pintype "bidirectional"))
      (node (ref "MICRO_UDB") (pin "Z3") (pinfunction "GND3_Z3") (pintype "bidirectional"))
      (node (ref "MICRO_UDB") (pin "Z4") (pinfunction "GND4_Z4") (pintype "bidirectional"))
      (node (ref "OK1") (pin "2") (pinfunction "C_2") (pintype "passive"))
      (node (ref "OK2") (pin "2") (pinfunction "C_2") (pintype "passive"))
      (node (ref "OK3") (pin "2") (pinfunction "C_2") (pintype "passive"))
      (node (ref "OK4") (pin "2") (pinfunction "C_2") (pintype "passive"))
      (node (ref "R4") (pin "1") (pinfunction "1_1") (pintype "passive"))
      (node (ref "R5") (pin "1") (pinfunction "1_1") (pintype "passive"))
      (node (ref "REGULATOR") (pin "1") (pinfunction "ADJ_1") (pintype "input"))
      (node (ref "RESET_SW") (pin "1") (pinfunction "1_1") (pintype "passive"))
      (node (ref "U3") (pin "4") (pinfunction "GND_4") (pintype "bidirectional"))
      (node (ref "X10") (pin "2") (pinfunction "KL_2") (pintype "passive"))
      (node (ref "X11") (pin "3") (pinfunction "KL_3") (pintype "passive"))
      (node (ref "X3") (pin "2") (pinfunction "KL_2") (pintype "passive"))
      (node (ref "X4") (pin "3") (pinfunction "KL_3") (pintype "passive"))
      (node (ref "X5") (pin "3") (pinfunction "KL_3") (pintype "passive"))
      (node (ref "X7") (pin "2") (pinfunction "KL_2") (pintype "passive"))
    )
    (net (code "60") (name "Net-(3.3V-PadA)") (class "Default")
      (node (ref "3.3V") (pin "A") (pinfunction "A_A") (pintype "passive"))
      (node (ref "R1") (pin "2") (pinfunction "2_2") (pintype "passive"))
    )
    (net (code "61") (name "Net-(5V-PadA)") (class "Default")
      (node (ref "5V") (pin "A") (pinfunction "A_A") (pintype "passive"))
      (node (ref "R2") (pin "2") (pinfunction "2_2") (pintype "passive"))
    )
    (net (code "62") (name "Net-(BT1-+)") (class "Default")
      (node (ref "BT1") (pin "1") (pinfunction "+_1") (pintype "power_in"))
      (node (ref "U3") (pin "3") (pinfunction "VBATT_3") (pintype "bidirectional"))
    )
    (net (code "63") (name "Net-(DATA-PadA)") (class "Default")
      (node (ref "DATA") (pin "A") (pinfunction "A_A") (pintype "passive"))
      (node (ref "R15") (pin "1") (pinfunction "1_1") (pintype "passive"))
    )
    (net (code "64") (name "Net-(ICTOUART-VBUS)") (class "Default")
      (node (ref "ICTOUART") (pin "8") (pinfunction "VBUS_8") (pintype "power_in"))
      (node (ref "R3") (pin "1") (pinfunction "1_1") (pintype "passive"))
      (node (ref "R4") (pin "2") (pinfunction "2_2") (pintype "passive"))
    )
    (net (code "65") (name "Net-(ICTOUART-~{RST})") (class "Default")
      (node (ref "ICTOUART") (pin "9") (pinfunction "~{RST}_9") (pintype "input"))
      (node (ref "R6") (pin "1") (pinfunction "1_1") (pintype "passive"))
    )
    (net (code "66") (name "Net-(ICTOUART-~{SUSPENDB})") (class "Default")
      (node (ref "ICTOUART") (pin "11") (pinfunction "~{SUSPENDB}_11") (pintype "output"))
      (node (ref "R5") (pin "2") (pinfunction "2_2") (pintype "passive"))
    )
    (net (code "67") (name "Net-(J28CA1-J2)") (class "Default")
      (node (ref "J28CA1") (pin "C") (pinfunction "J2_C") (pintype "bidirectional"))
      (node (ref "U$1") (pin "1") (pinfunction "P1_1") (pintype "input"))
      (node (ref "X3") (pin "1") (pinfunction "KL_1") (pintype "passive"))
    )
    (net (code "68") (name "Net-(J28CA4-J2)") (class "Default")
      (node (ref "J28CA4") (pin "C") (pinfunction "J2_C") (pintype "bidirectional"))
      (node (ref "U$2") (pin "1") (pinfunction "P1_1") (pintype "input"))
      (node (ref "X9") (pin "1") (pinfunction "KL_1") (pintype "passive"))
    )
    (net (code "69") (name "Net-(LEDO1-PadA)") (class "Default")
      (node (ref "LEDO1") (pin "A") (pinfunction "A_A") (pintype "passive"))
      (node (ref "R7") (pin "1") (pinfunction "1_1") (pintype "passive"))
    )
    (net (code "70") (name "Net-(LEDO2-PadA)") (class "Default")
      (node (ref "LEDO2") (pin "A") (pinfunction "A_A") (pintype "passive"))
      (node (ref "R11") (pin "1") (pinfunction "1_1") (pintype "passive"))
    )
    (net (code "71") (name "Net-(LEDO3-PadA)") (class "Default")
      (node (ref "LEDO3") (pin "A") (pinfunction "A_A") (pintype "passive"))
      (node (ref "R17") (pin "1") (pinfunction "1_1") (pintype "passive"))
    )
    (net (code "72") (name "Net-(LEDO4-PadA)") (class "Default")
      (node (ref "LEDO4") (pin "A") (pinfunction "A_A") (pintype "passive"))
      (node (ref "R20") (pin "1") (pinfunction "1_1") (pintype "passive"))
    )
    (net (code "73") (name "Net-(OK1-A)") (class "Default")
      (node (ref "OK1") (pin "1") (pinfunction "A_1") (pintype "passive"))
      (node (ref "R22") (pin "2") (pinfunction "2_2") (pintype "passive"))
    )
    (net (code "74") (name "Net-(OK1-EMIT)") (class "Default")
      (node (ref "OK1") (pin "3") (pinfunction "EMIT_3") (pintype "passive"))
      (node (ref "R18") (pin "2") (pinfunction "2_2") (pintype "passive"))
    )
    (net (code "75") (name "Net-(OK2-A)") (class "Default")
      (node (ref "OK2") (pin "1") (pinfunction "A_1") (pintype "passive"))
      (node (ref "R23") (pin "2") (pinfunction "2_2") (pintype "passive"))
    )
    (net (code "76") (name "Net-(OK2-EMIT)") (class "Default")
      (node (ref "OK2") (pin "3") (pinfunction "EMIT_3") (pintype "passive"))
      (node (ref "R10") (pin "2") (pinfunction "2_2") (pintype "passive"))
    )
    (net (code "77") (name "Net-(OK3-A)") (class "Default")
      (node (ref "OK3") (pin "1") (pinfunction "A_1") (pintype "passive"))
      (node (ref "R24") (pin "2") (pinfunction "2_2") (pintype "passive"))
    )
    (net (code "78") (name "Net-(OK3-EMIT)") (class "Default")
      (node (ref "OK3") (pin "3") (pinfunction "EMIT_3") (pintype "passive"))
      (node (ref "R19") (pin "2") (pinfunction "2_2") (pintype "passive"))
    )
    (net (code "79") (name "Net-(OK4-A)") (class "Default")
      (node (ref "OK4") (pin "1") (pinfunction "A_1") (pintype "passive"))
      (node (ref "R31") (pin "2") (pinfunction "2_2") (pintype "passive"))
    )
    (net (code "80") (name "Net-(OK4-EMIT)") (class "Default")
      (node (ref "OK4") (pin "3") (pinfunction "EMIT_3") (pintype "passive"))
      (node (ref "R21") (pin "2") (pinfunction "2_2") (pintype "passive"))
    )
    (net (code "81") (name "Net-(Q1-B)") (class "Default")
      (node (ref "Q1") (pin "1") (pinfunction "B_1") (pintype "passive"))
      (node (ref "R18") (pin "1") (pinfunction "1_1") (pintype "passive"))
    )
    (net (code "82") (name "Net-(Q1-C)") (class "Default")
      (node (ref "K1") (pin "2") (pinfunction "2_2") (pintype "passive"))
      (node (ref "Q1") (pin "3") (pinfunction "C_3") (pintype "passive"))
    )
    (net (code "83") (name "Net-(Q2-B)") (class "Default")
      (node (ref "Q2") (pin "1") (pinfunction "B_1") (pintype "passive"))
      (node (ref "R19") (pin "1") (pinfunction "1_1") (pintype "passive"))
    )
    (net (code "84") (name "Net-(Q2-C)") (class "Default")
      (node (ref "K2") (pin "2") (pinfunction "2_2") (pintype "passive"))
      (node (ref "Q2") (pin "3") (pinfunction "C_3") (pintype "passive"))
    )
    (net (code "85") (name "Net-(Q3-B)") (class "Default")
      (node (ref "Q3") (pin "1") (pinfunction "B_1") (pintype "passive"))
      (node (ref "R21") (pin "1") (pinfunction "1_1") (pintype "passive"))
    )
    (net (code "86") (name "Net-(Q3-C)") (class "Default")
      (node (ref "K3") (pin "2") (pinfunction "2_2") (pintype "passive"))
      (node (ref "Q3") (pin "3") (pinfunction "C_3") (pintype "passive"))
    )
    (net (code "87") (name "Net-(Q4-B)") (class "Default")
      (node (ref "Q4") (pin "1") (pinfunction "B_1") (pintype "passive"))
      (node (ref "R10") (pin "1") (pinfunction "1_1") (pintype "passive"))
    )
    (net (code "88") (name "Net-(Q4-C)") (class "Default")
      (node (ref "K4") (pin "2") (pinfunction "2_2") (pintype "passive"))
      (node (ref "Q4") (pin "3") (pinfunction "C_3") (pintype "passive"))
    )
    (net (code "89") (name "Net-(Q5-B)") (class "Default")
      (node (ref "Q5") (pin "1") (pinfunction "B_1") (pintype "passive"))
      (node (ref "R8") (pin "1") (pinfunction "1_1") (pintype "passive"))
    )
    (net (code "90") (name "Net-(Q6-B)") (class "Default")
      (node (ref "Q6") (pin "1") (pinfunction "B_1") (pintype "passive"))
      (node (ref "R9") (pin "1") (pinfunction "1_1") (pintype "passive"))
    )
    (net (code "91") (name "Net-(R14-Pad1)") (class "Default")
      (node (ref "R14") (pin "1") (pinfunction "1_1") (pintype "passive"))
      (node (ref "WIFI") (pin "A") (pinfunction "A_A") (pintype "passive"))
    )
    (net (code "92") (name "Net-(U$1-P$2)") (class "Default")
      (node (ref "D3") (pin "A") (pinfunction "A_A") (pintype "passive"))
      (node (ref "U$1") (pin "2") (pinfunction "P$2_2") (pintype "output"))
    )
    (net (code "93") (name "Net-(U$2-P$2)") (class "Default")
      (node (ref "D2") (pin "A") (pinfunction "A_A") (pintype "passive"))
      (node (ref "U$2") (pin "2") (pinfunction "P$2_2") (pintype "output"))
    )
    (net (code "94") (name "Net-(U3-X1)") (class "Default")
      (node (ref "32.768KHZ") (pin "2") (pinfunction "2_2") (pintype "passive"))
      (node (ref "U3") (pin "1") (pinfunction "X1_1") (pintype "bidirectional"))
    )
    (net (code "95") (name "Net-(U3-X2)") (class "Default")
      (node (ref "32.768KHZ") (pin "1") (pinfunction "1_1") (pintype "passive"))
      (node (ref "U3") (pin "2") (pinfunction "X2_2") (pintype "bidirectional"))
    )
    (net (code "96") (name "unconnected-(ANT1-NC-Pad32)") (class "Default")
      (node (ref "ANT1") (pin "32") (pinfunction "NC_32") (pintype "no_connect"))
    )
    (net (code "97") (name "unconnected-(FLASH_SW-Pad2)") (class "Default")
      (node (ref "FLASH_SW") (pin "2") (pinfunction "2_2") (pintype "passive"))
    )
    (net (code "98") (name "unconnected-(FLASH_SW-Pad4)") (class "Default")
      (node (ref "FLASH_SW") (pin "4") (pinfunction "4_4") (pintype "passive"))
    )
    (net (code "99") (name "unconnected-(ICTOUART-CHR0-Pad15)") (class "Default")
      (node (ref "ICTOUART") (pin "15") (pinfunction "CHR0_15") (pintype "output"))
    )
    (net (code "100") (name "unconnected-(ICTOUART-CHR1-Pad14)") (class "Default")
      (node (ref "ICTOUART") (pin "14") (pinfunction "CHR1_14") (pintype "output"))
    )
    (net (code "101") (name "unconnected-(ICTOUART-CHREN-Pad13)") (class "Default")
      (node (ref "ICTOUART") (pin "13") (pinfunction "CHREN_13") (pintype "output"))
    )
    (net (code "102") (name "unconnected-(ICTOUART-CTS-Pad23)") (class "Default")
      (node (ref "ICTOUART") (pin "23") (pinfunction "CTS_23") (pintype "input"))
    )
    (net (code "103") (name "unconnected-(ICTOUART-DCD-Pad1)") (class "Default")
      (node (ref "ICTOUART") (pin "1") (pinfunction "DCD_1") (pintype "input"))
    )
    (net (code "104") (name "unconnected-(ICTOUART-DSR-Pad27)") (class "Default")
      (node (ref "ICTOUART") (pin "27") (pinfunction "DSR_27") (pintype "input"))
    )
    (net (code "105") (name "unconnected-(ICTOUART-GPIO.0{slash}TXT-Pad19)") (class "Default")
      (node (ref "ICTOUART") (pin "19") (pinfunction "GPIO.0/TXT_19") (pintype "bidirectional"))
    )
    (net (code "106") (name "unconnected-(ICTOUART-GPIO.1{slash}RXT-Pad18)") (class "Default")
      (node (ref "ICTOUART") (pin "18") (pinfunction "GPIO.1/RXT_18") (pintype "bidirectional"))
    )
    (net (code "107") (name "unconnected-(ICTOUART-GPIO.2{slash}RS485-Pad17)") (class "Default")
      (node (ref "ICTOUART") (pin "17") (pinfunction "GPIO.2/RS485_17") (pintype "bidirectional"))
    )
    (net (code "108") (name "unconnected-(ICTOUART-GPIO.3{slash}WAKEUP-Pad16)") (class "Default")
      (node (ref "ICTOUART") (pin "16") (pinfunction "GPIO.3/WAKEUP_16") (pintype "bidirectional"))
    )
    (net (code "109") (name "unconnected-(ICTOUART-GPIO.4-Pad22)") (class "Default")
      (node (ref "ICTOUART") (pin "22") (pinfunction "GPIO.4_22") (pintype "bidirectional"))
    )
    (net (code "110") (name "unconnected-(ICTOUART-GPIO.5-Pad21)") (class "Default")
      (node (ref "ICTOUART") (pin "21") (pinfunction "GPIO.5_21") (pintype "bidirectional"))
    )
    (net (code "111") (name "unconnected-(ICTOUART-GPIO.6-Pad20)") (class "Default")
      (node (ref "ICTOUART") (pin "20") (pinfunction "GPIO.6_20") (pintype "bidirectional"))
    )
    (net (code "112") (name "unconnected-(ICTOUART-RI{slash}CLK-Pad2)") (class "Default")
      (node (ref "ICTOUART") (pin "2") (pinfunction "RI/CLK_2") (pintype "bidirectional"))
    )
    (net (code "113") (name "unconnected-(ICTOUART-SUSPEND-Pad12)") (class "Default")
      (node (ref "ICTOUART") (pin "12") (pinfunction "SUSPEND_12") (pintype "output"))
    )
    (net (code "114") (name "unconnected-(IO35_SW-Pad2)") (class "Default")
      (node (ref "IO35_SW") (pin "2") (pinfunction "2_2") (pintype "passive"))
    )
    (net (code "115") (name "unconnected-(IO35_SW-Pad4)") (class "Default")
      (node (ref "IO35_SW") (pin "4") (pinfunction "4_4") (pintype "passive"))
    )
    (net (code "116") (name "unconnected-(J2-CTS-Pad5)") (class "Default")
      (node (ref "J2") (pin "5") (pinfunction "CTS_5") (pintype "passive"))
    )
    (net (code "117") (name "unconnected-(J2-DTR-Pad1)") (class "Default")
      (node (ref "J2") (pin "1") (pinfunction "DTR_1") (pintype "passive"))
    )
    (net (code "118") (name "unconnected-(RESET_SW-Pad2)") (class "Default")
      (node (ref "RESET_SW") (pin "2") (pinfunction "2_2") (pintype "passive"))
    )
    (net (code "119") (name "unconnected-(RESET_SW-Pad4)") (class "Default")
      (node (ref "RESET_SW") (pin "4") (pinfunction "4_4") (pintype "passive"))
    )
    (net (code "120") (name "unconnected-(U3-SQW-Pad7)") (class "Default")
      (node (ref "U3") (pin "7") (pinfunction "SQW_7") (pintype "bidirectional"))
    )
  )
)
